# AlcoTop.net
KiCad netlist of a schematic drawn in EAGLE
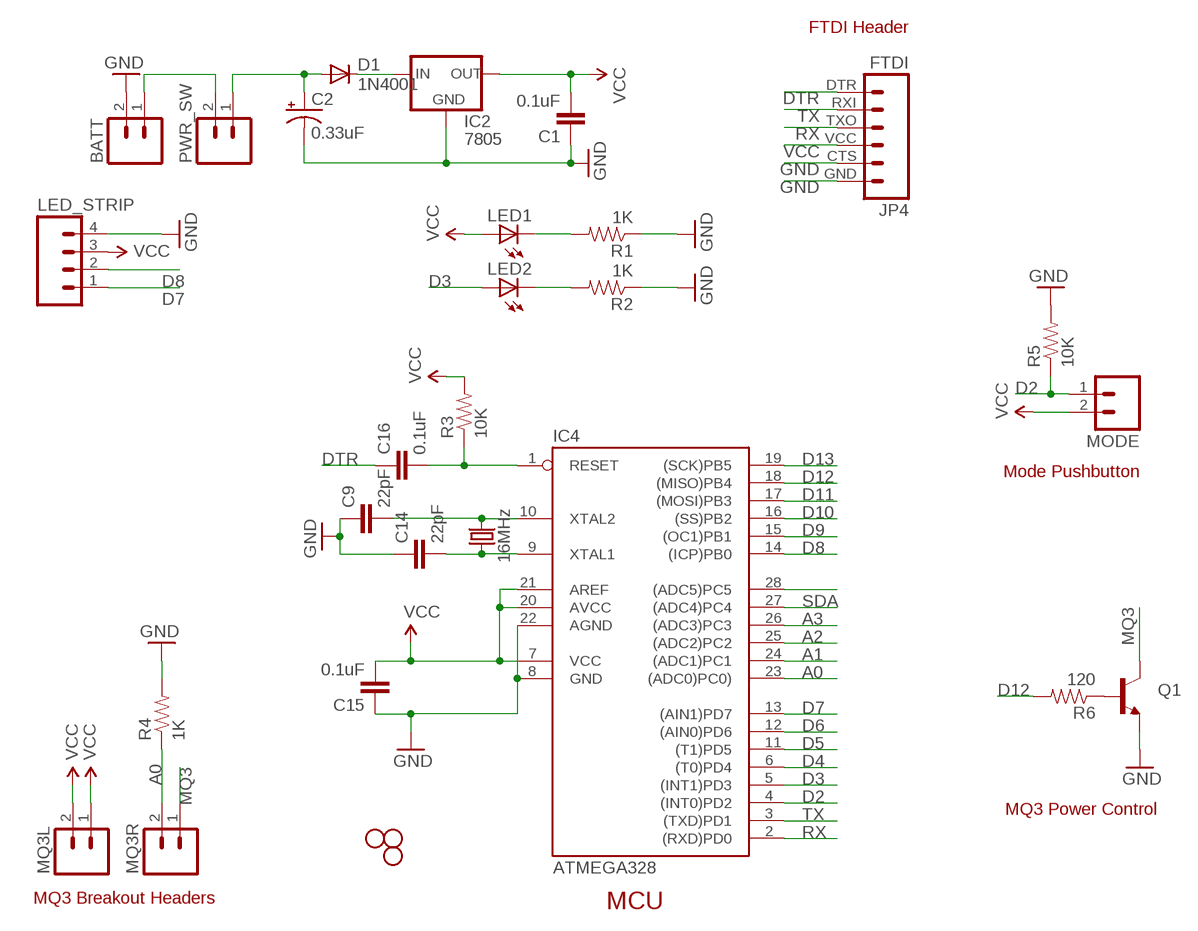
[diagram p0: schematic, sheet 1]

(export (version "E")
  (design (tool "Eeschema 10.0.6"))
  (components
    (comp (ref "BATT")
      (value "M02LOCK_LONGPADS")
      (footprint "eagle-import:1X02_LOCK_LONGPADS")
      (libsource (lib "eagle-import") (part "M02LOCK_LONGPADS"))
    )
    (comp (ref "C1")
      (value "0.1uF")
      (footprint "eagle-import:CAP-PTH-SMALL2")
      (libsource (lib "eagle-import") (part "CAPPTH2"))
    )
    (comp (ref "C2")
      (value "0.33uF")
      (footprint "eagle-import:CPOL-RADIAL-10UF-25V")
      (libsource (lib "eagle-import") (part "CAP_POLPTH2"))
    )
    (comp (ref "C9")
      (value "22pF")
      (footprint "eagle-import:CAP-PTH-SMALL2")
      (libsource (lib "eagle-import") (part "CAPPTH2"))
    )
    (comp (ref "C14")
      (value "22pF")
      (footprint "eagle-import:CAP-PTH-SMALL2")
      (libsource (lib "eagle-import") (part "CAPPTH2"))
    )
    (comp (ref "C15")
      (value "0.1uF")
      (footprint "eagle-import:CAP-PTH-SMALL2")
      (libsource (lib "eagle-import") (part "CAPPTH2"))
    )
    (comp (ref "C16")
      (value "0.1uF")
      (footprint "eagle-import:CAP-PTH-SMALL2")
      (libsource (lib "eagle-import") (part "CAPPTH2"))
    )
    (comp (ref "D1")
      (value "1N4001")
      (footprint "eagle-import:DIODE-1N4001")
      (libsource (lib "eagle-import") (part "DIODEPTH"))
    )
    (comp (ref "IC2")
      (value "7805")
      (footprint "eagle-import:TO220-IGO")
      (libsource (lib "eagle-import") (part "V_REG_78XXSINK"))
    )
    (comp (ref "IC4")
      (value "ATMEGA328")
      (footprint "eagle-import:DIL28-3")
      (libsource (lib "eagle-import") (part "AT90S4433P"))
    )
    (comp (ref "JP1")
      (value "STAND-OFF#2")
      (footprint "eagle-import:STAND-OFF-#2")
      (libsource (lib "eagle-import") (part "STAND-OFF#2"))
    )
    (comp (ref "JP2")
      (value "STAND-OFF#2")
      (footprint "eagle-import:STAND-OFF-#2")
      (libsource (lib "eagle-import") (part "STAND-OFF#2"))
    )
    (comp (ref "JP4")
      (value "FTDI")
      (footprint "eagle-import:FTDI_BASIC")
      (libsource (lib "eagle-import") (part "FTDI_BASICPTH"))
    )
    (comp (ref "JP6")
      (value "STAND-OFF#2")
      (footprint "eagle-import:STAND-OFF-#2")
      (libsource (lib "eagle-import") (part "STAND-OFF#2"))
    )
    (comp (ref "LED1")
      (value "LED5MM")
      (footprint "eagle-import:LED5MM")
      (libsource (lib "eagle-import") (part "LED5MM"))
    )
    (comp (ref "LED2")
      (value "LED5MM")
      (footprint "eagle-import:LED5MM")
      (libsource (lib "eagle-import") (part "LED5MM"))
    )
    (comp (ref "LED_STRIP")
      (value "M04LOCK_LONGPADS")
      (footprint "eagle-import:1X04_LOCK_LONGPADS")
      (libsource (lib "eagle-import") (part "M04LOCK_LONGPADS"))
    )
    (comp (ref "MODE")
      (value "M02LOCK_LONGPADS")
      (footprint "eagle-import:1X02_LOCK_LONGPADS")
      (libsource (lib "eagle-import") (part "M02LOCK_LONGPADS"))
    )
    (comp (ref "MQ3L")
      (value "M02LOCK_LONGPADS")
      (footprint "eagle-import:1X02_LOCK_LONGPADS")
      (libsource (lib "eagle-import") (part "M02LOCK_LONGPADS"))
    )
    (comp (ref "MQ3R")
      (value "M02LOCK_LONGPADS")
      (footprint "eagle-import:1X02_LOCK_LONGPADS")
      (libsource (lib "eagle-import") (part "M02LOCK_LONGPADS"))
    )
    (comp (ref "PWR_SW")
      (value "M02LOCK_LONGPADS")
      (footprint "eagle-import:1X02_LOCK_LONGPADS")
      (libsource (lib "eagle-import") (part "M02LOCK_LONGPADS"))
    )
    (comp (ref "Q1")
      (value "TRANSISTOR_NPNTO-92-AMMO")
      (footprint "eagle-import:TO-92-AMMO")
      (libsource (lib "eagle-import") (part "TRANSISTOR_NPNTO-92-AMMO"))
    )
    (comp (ref "R1")
      (value "1K")
      (footprint "eagle-import:AXIAL-0.3")
      (libsource (lib "eagle-import") (part "RESISTORAXIAL-0.3"))
    )
    (comp (ref "R2")
      (value "1K")
      (footprint "eagle-import:AXIAL-0.3")
      (libsource (lib "eagle-import") (part "RESISTORAXIAL-0.3"))
    )
    (comp (ref "R3")
      (value "10K")
      (footprint "eagle-import:AXIAL-0.3")
      (libsource (lib "eagle-import") (part "RESISTORAXIAL-0.3"))
    )
    (comp (ref "R4")
      (value "1K")
      (footprint "eagle-import:AXIAL-0.3")
      (libsource (lib "eagle-import") (part "RESISTORAXIAL-0.3"))
    )
    (comp (ref "R5")
      (value "10K")
      (footprint "eagle-import:AXIAL-0.3")
      (libsource (lib "eagle-import") (part "RESISTORAXIAL-0.3"))
    )
    (comp (ref "R6")
      (value "120")
      (footprint "eagle-import:AXIAL-0.3")
      (libsource (lib "eagle-import") (part "RESISTORAXIAL-0.3"))
    )
    (comp (ref "Y1")
      (value "16MHz")
      (footprint "eagle-import:HC49US")
      (libsource (lib "eagle-import") (part "CRYSTALHC49US"))
    )
  )
  (nets
    (net (code "1") (name "/A0") (class "Default")
      (node (ref "IC4") (pin "23") (pinfunction "(ADC0)PC0)_23") (pintype "bidirectional"))
      (node (ref "MQ3R") (pin "2") (pinfunction "2_2") (pintype "passive"))
      (node (ref "R4") (pin "P$1") (pinfunction "1_P$1") (pintype "passive"))
    )
    (net (code "2") (name "/A1") (class "Default")
      (node (ref "IC4") (pin "24") (pinfunction "(ADC1)PC1_24") (pintype "bidirectional"))
    )
    (net (code "3") (name "/A2") (class "Default")
      (node (ref "IC4") (pin "25") (pinfunction "(ADC2)PC2_25") (pintype "bidirectional"))
    )
    (net (code "4") (name "/A3") (class "Default")
      (node (ref "IC4") (pin "26") (pinfunction "(ADC3)PC3_26") (pintype "bidirectional"))
    )
    (net (code "5") (name "/D2") (class "Default")
      (node (ref "IC4") (pin "4") (pinfunction "(INT0)PD2_4") (pintype "bidirectional"))
      (node (ref "MODE") (pin "1") (pinfunction "1_1") (pintype "passive"))
      (node (ref "R5") (pin "P$1") (pinfunction "1_P$1") (pintype "passive"))
    )
    (net (code "6") (name "/D3") (class "Default")
      (node (ref "IC4") (pin "5") (pinfunction "(INT1)PD3_5") (pintype "bidirectional"))
      (node (ref "LED2") (pin "A") (pinfunction "A_A") (pintype "passive"))
    )
    (net (code "7") (name "/D4") (class "Default")
      (node (ref "IC4") (pin "6") (pinfunction "(T0)PD4_6") (pintype "bidirectional"))
    )
    (net (code "8") (name "/D5") (class "Default")
      (node (ref "IC4") (pin "11") (pinfunction "(T1)PD5_11") (pintype "bidirectional"))
    )
    (net (code "9") (name "/D6") (class "Default")
      (node (ref "IC4") (pin "12") (pinfunction "(AIN0)PD6_12") (pintype "bidirectional"))
    )
    (net (code "10") (name "/D7") (class "Default")
      (node (ref "IC4") (pin "13") (pinfunction "(AIN1)PD7_13") (pintype "bidirectional"))
      (node (ref "LED_STRIP") (pin "1") (pinfunction "1_1") (pintype "passive"))
    )
    (net (code "11") (name "/D8") (class "Default")
      (node (ref "IC4") (pin "14") (pinfunction "(ICP)PB0_14") (pintype "bidirectional"))
      (node (ref "LED_STRIP") (pin "2") (pinfunction "2_2") (pintype "passive"))
    )
    (net (code "12") (name "/D9") (class "Default")
      (node (ref "IC4") (pin "15") (pinfunction "(OC1)PB1_15") (pintype "bidirectional"))
    )
    (net (code "13") (name "/D10") (class "Default")
      (node (ref "IC4") (pin "16") (pinfunction "(SS)PB2_16") (pintype "bidirectional"))
    )
    (net (code "14") (name "/D11") (class "Default")
      (node (ref "IC4") (pin "17") (pinfunction "(MOSI)PB3_17") (pintype "bidirectional"))
    )
    (net (code "15") (name "/D12") (class "Default")
      (node (ref "IC4") (pin "18") (pinfunction "(MISO)PB4_18") (pintype "bidirectional"))
      (node (ref "R6") (pin "P$2") (pinfunction "2_P$2") (pintype "passive"))
    )
    (net (code "16") (name "/D13") (class "Default")
      (node (ref "IC4") (pin "19") (pinfunction "(SCK)PB5_19") (pintype "bidirectional"))
    )
    (net (code "17") (name "/DTR") (class "Default")
      (node (ref "C16") (pin "1") (pinfunction "1_1") (pintype "passive"))
      (node (ref "JP4") (pin "DTR") (pinfunction "1_DTR") (pintype "passive"))
    )
    (net (code "18") (name "/MQ3") (class "Default")
      (node (ref "MQ3R") (pin "1") (pinfunction "1_1") (pintype "passive"))
      (node (ref "Q1") (pin "3") (pinfunction "C_3") (pintype "passive"))
    )
    (net (code "19") (name "/RX") (class "Default")
      (node (ref "IC4") (pin "2") (pinfunction "(RXD)PD0_2") (pintype "bidirectional"))
      (node (ref "JP4") (pin "TXO") (pinfunction "3_TXO") (pintype "passive"))
    )
    (net (code "20") (name "/SDA") (class "Default")
      (node (ref "IC4") (pin "27") (pinfunction "(ADC4)PC4_27") (pintype "bidirectional"))
    )
    (net (code "21") (name "/TX") (class "Default")
      (node (ref "IC4") (pin "3") (pinfunction "(TXD)PD1_3") (pintype "bidirectional"))
      (node (ref "JP4") (pin "RXI") (pinfunction "2_RXI") (pintype "passive"))
    )
    (net (code "22") (name "GND") (class "Default")
      (node (ref "BATT") (pin "2") (pinfunction "2_2") (pintype "passive"))
      (node (ref "C1") (pin "1") (pinfunction "1_1") (pintype "passive"))
      (node (ref "C14") (pin "1") (pinfunction "1_1") (pintype "passive"))
      (node (ref "C15") (pin "1") (pinfunction "1_1") (pintype "passive"))
      (node (ref "C2") (pin "2") (pinfunction "-_2") (pintype "passive"))
      (node (ref "C9") (pin "1") (pinfunction "1_1") (pintype "passive"))
      (node (ref "IC2") (pin "GND") (pinfunction "GND_GND") (pintype "input"))
      (node (ref "IC4") (pin "22") (pinfunction "AGND_22") (pintype "power_in"))
      (node (ref "IC4") (pin "8") (pinfunction "GND_8") (pintype "power_in"))
      (node (ref "JP4") (pin "CTS") (pinfunction "5_CTS") (pintype "passive"))
      (node (ref "JP4") (pin "GND") (pinfunction "6_GND") (pintype "passive"))
      (node (ref "LED_STRIP") (pin "4") (pinfunction "4_4") (pintype "passive"))
      (node (ref "Q1") (pin "1") (pinfunction "E_1") (pintype "passive"))
      (node (ref "R1") (pin "P$1") (pinfunction "1_P$1") (pintype "passive"))
      (node (ref "R2") (pin "P$1") (pinfunction "1_P$1") (pintype "passive"))
      (node (ref "R4") (pin "P$2") (pinfunction "2_P$2") (pintype "passive"))
      (node (ref "R5") (pin "P$2") (pinfunction "2_P$2") (pintype "passive"))
    )
    (net (code "23") (name "Net-(BATT-Pad1)") (class "Default")
      (node (ref "BATT") (pin "1") (pinfunction "1_1") (pintype "passive"))
      (node (ref "PWR_SW") (pin "2") (pinfunction "2_2") (pintype "passive"))
    )
    (net (code "24") (name "Net-(C2-+)") (class "Default")
      (node (ref "C2") (pin "1") (pinfunction "+_1") (pintype "passive"))
      (node (ref "D1") (pin "A") (pinfunction "A_A") (pintype "passive"))
      (node (ref "PWR_SW") (pin "1") (pinfunction "1_1") (pintype "passive"))
    )
    (net (code "25") (name "Net-(D1-PadC)") (class "Default")
      (node (ref "D1") (pin "C") (pinfunction "C_C") (pintype "passive"))
      (node (ref "IC2") (pin "IN") (pinfunction "IN_IN") (pintype "input"))
    )
    (net (code "26") (name "Net-(IC4-RESET)") (class "Default")
      (node (ref "C16") (pin "2") (pinfunction "2_2") (pintype "passive"))
      (node (ref "IC4") (pin "1") (pinfunction "RESET_1") (pintype "input"))
      (node (ref "R3") (pin "P$1") (pinfunction "1_P$1") (pintype "passive"))
    )
    (net (code "27") (name "Net-(IC4-XTAL1)") (class "Default")
      (node (ref "C14") (pin "2") (pinfunction "2_2") (pintype "passive"))
      (node (ref "IC4") (pin "9") (pinfunction "XTAL1_9") (pintype "bidirectional"))
      (node (ref "Y1") (pin "1") (pinfunction "1_1") (pintype "passive"))
    )
    (net (code "28") (name "Net-(IC4-XTAL2)") (class "Default")
      (node (ref "C9") (pin "2") (pinfunction "2_2") (pintype "passive"))
      (node (ref "IC4") (pin "10") (pinfunction "XTAL2_10") (pintype "bidirectional"))
      (node (ref "Y1") (pin "2") (pinfunction "2_2") (pintype "passive"))
    )
    (net (code "29") (name "Net-(LED1-C)") (class "Default")
      (node (ref "LED1") (pin "K") (pinfunction "C_K") (pintype "passive"))
      (node (ref "R1") (pin "P$2") (pinfunction "2_P$2") (pintype "passive"))
    )
    (net (code "30") (name "Net-(LED2-C)") (class "Default")
      (node (ref "LED2") (pin "K") (pinfunction "C_K") (pintype "passive"))
      (node (ref "R2") (pin "P$2") (pinfunction "2_P$2") (pintype "passive"))
    )
    (net (code "31") (name "Net-(Q1-B)") (class "Default")
      (node (ref "Q1") (pin "2") (pinfunction "B_2") (pintype "passive"))
      (node (ref "R6") (pin "P$1") (pinfunction "1_P$1") (pintype "passive"))
    )
    (net (code "32") (name "VCC") (class "Default")
      (node (ref "C1") (pin "2") (pinfunction "2_2") (pintype "passive"))
      (node (ref "C15") (pin "2") (pinfunction "2_2") (pintype "passive"))
      (node (ref "IC2") (pin "OUT") (pinfunction "OUT_OUT") (pintype "output"))
      (node (ref "IC4") (pin "20") (pinfunction "AVCC_20") (pintype "power_in"))
      (node (ref "IC4") (pin "21") (pinfunction "AREF_21") (pintype "passive"))
      (node (ref "IC4") (pin "7") (pinfunction "VCC_7") (pintype "power_in"))
      (node (ref "JP4") (pin "VCC") (pinfunction "4_VCC") (pintype "passive"))
      (node (ref "LED1") (pin "A") (pinfunction "A_A") (pintype "passive"))
      (node (ref "LED_STRIP") (pin "3") (pinfunction "3_3") (pintype "passive"))
      (node (ref "MODE") (pin "2") (pinfunction "2_2") (pintype "passive"))
      (node (ref "MQ3L") (pin "1") (pinfunction "1_1") (pintype "passive"))
      (node (ref "MQ3L") (pin "2") (pinfunction "2_2") (pintype "passive"))
      (node (ref "R3") (pin "P$2") (pinfunction "2_P$2") (pintype "passive"))
    )
    (net (code "33") (name "unconnected-(IC4-(ADC5)PC5-Pad28)") (class "Default")
      (node (ref "IC4") (pin "28") (pinfunction "(ADC5)PC5_28") (pintype "bidirectional"))
    )
  )
)
